# Sensor_HallArray.net
KiCad netlist of a schematic drawn in EAGLE
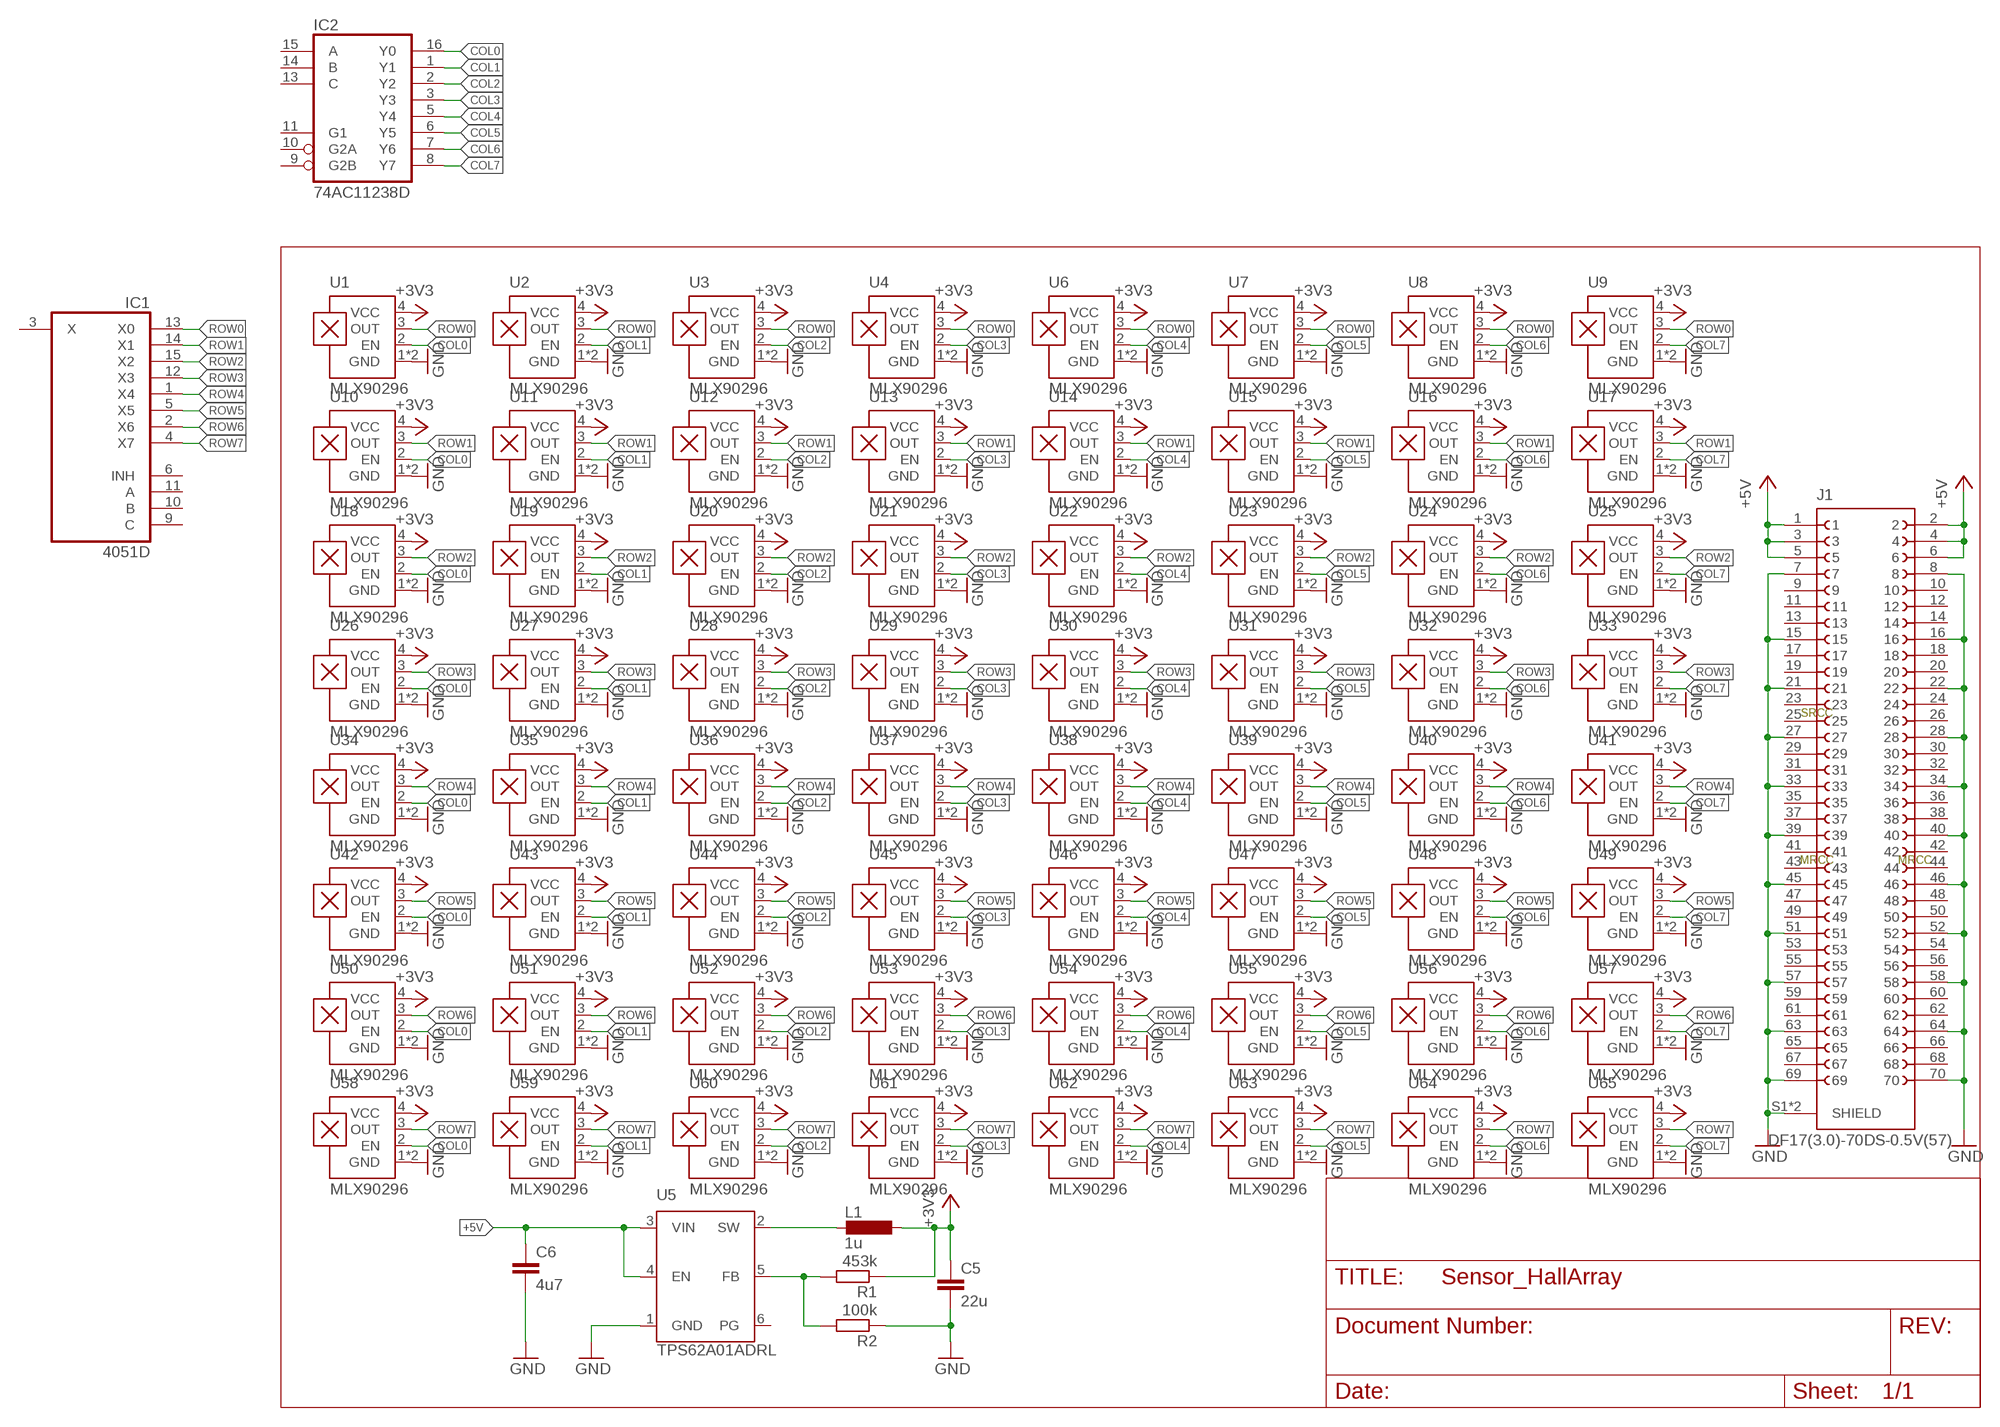
[diagram p0: schematic, sheet 1]

(export (version "E")
  (design (tool "Eeschema 10.0.6"))
  (components
    (comp (ref "C5")
      (value "22u")
      (footprint "eagle-import:C0603")
      (libsource (lib "eagle-import") (part "C-EUC0603"))
    )
    (comp (ref "C6")
      (value "4u7")
      (footprint "eagle-import:C0603")
      (libsource (lib "eagle-import") (part "C-EUC0603"))
    )
    (comp (ref "IC1")
      (value "4051D")
      (footprint "eagle-import:SO16")
      (libsource (lib "eagle-import") (part "4051D"))
    )
    (comp (ref "IC2")
      (value "74AC11238D")
      (footprint "eagle-import:SO16")
      (libsource (lib "eagle-import") (part "74AC11238D"))
    )
    (comp (ref "J1")
      (value "DF17(3.0)-70DS-0.5V(57)")
      (footprint "eagle-import:DF17(3.0)-70DS-0.5V(57)")
      (libsource (lib "eagle-import") (part "DF17(3.0)-70DS-0.5V(57)"))
    )
    (comp (ref "L1")
      (value "1u")
      (footprint "eagle-import:L1008")
      (fields (field (name "MPN") "LQM2HPN1R0MG0L"))
      (libsource (lib "eagle-import") (part "L-EU1008"))
    )
    (comp (ref "R1")
      (value "453k")
      (footprint "eagle-import:R0402")
      (libsource (lib "eagle-import") (part "R-EU_R0402"))
    )
    (comp (ref "R2")
      (value "100k")
      (footprint "eagle-import:R0402")
      (libsource (lib "eagle-import") (part "R-EU_R0402"))
    )
    (comp (ref "U1")
      (value "MLX90296")
      (footprint "eagle-import:DFN120X160X40-4")
      (libsource (lib "eagle-import") (part "MLX90296"))
    )
    (comp (ref "U2")
      (value "MLX90296")
      (footprint "eagle-import:DFN120X160X40-4")
      (libsource (lib "eagle-import") (part "MLX90296"))
    )
    (comp (ref "U3")
      (value "MLX90296")
      (footprint "eagle-import:DFN120X160X40-4")
      (libsource (lib "eagle-import") (part "MLX90296"))
    )
    (comp (ref "U4")
      (value "MLX90296")
      (footprint "eagle-import:DFN120X160X40-4")
      (libsource (lib "eagle-import") (part "MLX90296"))
    )
    (comp (ref "U5")
      (value "TPS62A01ADRL")
      (footprint "eagle-import:SOTFL50P160X60-6N")
      (fields (field (name "MANUFACTURER_PART_NUMBER") "TPS62A01ADRLR"))
      (libsource (lib "eagle-import") (part "TPS62A01ADRL"))
    )
    (comp (ref "U6")
      (value "MLX90296")
      (footprint "eagle-import:DFN120X160X40-4")
      (libsource (lib "eagle-import") (part "MLX90296"))
    )
    (comp (ref "U7")
      (value "MLX90296")
      (footprint "eagle-import:DFN120X160X40-4")
      (libsource (lib "eagle-import") (part "MLX90296"))
    )
    (comp (ref "U8")
      (value "MLX90296")
      (footprint "eagle-import:DFN120X160X40-4")
      (libsource (lib "eagle-import") (part "MLX90296"))
    )
    (comp (ref "U9")
      (value "MLX90296")
      (footprint "eagle-import:DFN120X160X40-4")
      (libsource (lib "eagle-import") (part "MLX90296"))
    )
    (comp (ref "U10")
      (value "MLX90296")
      (footprint "eagle-import:DFN120X160X40-4")
      (libsource (lib "eagle-import") (part "MLX90296"))
    )
    (comp (ref "U11")
      (value "MLX90296")
      (footprint "eagle-import:DFN120X160X40-4")
      (libsource (lib "eagle-import") (part "MLX90296"))
    )
    (comp (ref "U12")
      (value "MLX90296")
      (footprint "eagle-import:DFN120X160X40-4")
      (libsource (lib "eagle-import") (part "MLX90296"))
    )
    (comp (ref "U13")
      (value "MLX90296")
      (footprint "eagle-import:DFN120X160X40-4")
      (libsource (lib "eagle-import") (part "MLX90296"))
    )
    (comp (ref "U14")
      (value "MLX90296")
      (footprint "eagle-import:DFN120X160X40-4")
      (libsource (lib "eagle-import") (part "MLX90296"))
    )
    (comp (ref "U15")
      (value "MLX90296")
      (footprint "eagle-import:DFN120X160X40-4")
      (libsource (lib "eagle-import") (part "MLX90296"))
    )
    (comp (ref "U16")
      (value "MLX90296")
      (footprint "eagle-import:DFN120X160X40-4")
      (libsource (lib "eagle-import") (part "MLX90296"))
    )
    (comp (ref "U17")
      (value "MLX90296")
      (footprint "eagle-import:DFN120X160X40-4")
      (libsource (lib "eagle-import") (part "MLX90296"))
    )
    (comp (ref "U18")
      (value "MLX90296")
      (footprint "eagle-import:DFN120X160X40-4")
      (libsource (lib "eagle-import") (part "MLX90296"))
    )
    (comp (ref "U19")
      (value "MLX90296")
      (footprint "eagle-import:DFN120X160X40-4")
      (libsource (lib "eagle-import") (part "MLX90296"))
    )
    (comp (ref "U20")
      (value "MLX90296")
      (footprint "eagle-import:DFN120X160X40-4")
      (libsource (lib "eagle-import") (part "MLX90296"))
    )
    (comp (ref "U21")
      (value "MLX90296")
      (footprint "eagle-import:DFN120X160X40-4")
      (libsource (lib "eagle-import") (part "MLX90296"))
    )
    (comp (ref "U22")
      (value "MLX90296")
      (footprint "eagle-import:DFN120X160X40-4")
      (libsource (lib "eagle-import") (part "MLX90296"))
    )
    (comp (ref "U23")
      (value "MLX90296")
      (footprint "eagle-import:DFN120X160X40-4")
      (libsource (lib "eagle-import") (part "MLX90296"))
    )
    (comp (ref "U24")
      (value "MLX90296")
      (footprint "eagle-import:DFN120X160X40-4")
      (libsource (lib "eagle-import") (part "MLX90296"))
    )
    (comp (ref "U25")
      (value "MLX90296")
      (footprint "eagle-import:DFN120X160X40-4")
      (libsource (lib "eagle-import") (part "MLX90296"))
    )
    (comp (ref "U26")
      (value "MLX90296")
      (footprint "eagle-import:DFN120X160X40-4")
      (libsource (lib "eagle-import") (part "MLX90296"))
    )
    (comp (ref "U27")
      (value "MLX90296")
      (footprint "eagle-import:DFN120X160X40-4")
      (libsource (lib "eagle-import") (part "MLX90296"))
    )
    (comp (ref "U28")
      (value "MLX90296")
      (footprint "eagle-import:DFN120X160X40-4")
      (libsource (lib "eagle-import") (part "MLX90296"))
    )
    (comp (ref "U29")
      (value "MLX90296")
      (footprint "eagle-import:DFN120X160X40-4")
      (libsource (lib "eagle-import") (part "MLX90296"))
    )
    (comp (ref "U30")
      (value "MLX90296")
      (footprint "eagle-import:DFN120X160X40-4")
      (libsource (lib "eagle-import") (part "MLX90296"))
    )
    (comp (ref "U31")
      (value "MLX90296")
      (footprint "eagle-import:DFN120X160X40-4")
      (libsource (lib "eagle-import") (part "MLX90296"))
    )
    (comp (ref "U32")
      (value "MLX90296")
      (footprint "eagle-import:DFN120X160X40-4")
      (libsource (lib "eagle-import") (part "MLX90296"))
    )
    (comp (ref "U33")
      (value "MLX90296")
      (footprint "eagle-import:DFN120X160X40-4")
      (libsource (lib "eagle-import") (part "MLX90296"))
    )
    (comp (ref "U34")
      (value "MLX90296")
      (footprint "eagle-import:DFN120X160X40-4")
      (libsource (lib "eagle-import") (part "MLX90296"))
    )
    (comp (ref "U35")
      (value "MLX90296")
      (footprint "eagle-import:DFN120X160X40-4")
      (libsource (lib "eagle-import") (part "MLX90296"))
    )
    (comp (ref "U36")
      (value "MLX90296")
      (footprint "eagle-import:DFN120X160X40-4")
      (libsource (lib "eagle-import") (part "MLX90296"))
    )
    (comp (ref "U37")
      (value "MLX90296")
      (footprint "eagle-import:DFN120X160X40-4")
      (libsource (lib "eagle-import") (part "MLX90296"))
    )
    (comp (ref "U38")
      (value "MLX90296")
      (footprint "eagle-import:DFN120X160X40-4")
      (libsource (lib "eagle-import") (part "MLX90296"))
    )
    (comp (ref "U39")
      (value "MLX90296")
      (footprint "eagle-import:DFN120X160X40-4")
      (libsource (lib "eagle-import") (part "MLX90296"))
    )
    (comp (ref "U40")
      (value "MLX90296")
      (footprint "eagle-import:DFN120X160X40-4")
      (libsource (lib "eagle-import") (part "MLX90296"))
    )
    (comp (ref "U41")
      (value "MLX90296")
      (footprint "eagle-import:DFN120X160X40-4")
      (libsource (lib "eagle-import") (part "MLX90296"))
    )
    (comp (ref "U42")
      (value "MLX90296")
      (footprint "eagle-import:DFN120X160X40-4")
      (libsource (lib "eagle-import") (part "MLX90296"))
    )
    (comp (ref "U43")
      (value "MLX90296")
      (footprint "eagle-import:DFN120X160X40-4")
      (libsource (lib "eagle-import") (part "MLX90296"))
    )
    (comp (ref "U44")
      (value "MLX90296")
      (footprint "eagle-import:DFN120X160X40-4")
      (libsource (lib "eagle-import") (part "MLX90296"))
    )
    (comp (ref "U45")
      (value "MLX90296")
      (footprint "eagle-import:DFN120X160X40-4")
      (libsource (lib "eagle-import") (part "MLX90296"))
    )
    (comp (ref "U46")
      (value "MLX90296")
      (footprint "eagle-import:DFN120X160X40-4")
      (libsource (lib "eagle-import") (part "MLX90296"))
    )
    (comp (ref "U47")
      (value "MLX90296")
      (footprint "eagle-import:DFN120X160X40-4")
      (libsource (lib "eagle-import") (part "MLX90296"))
    )
    (comp (ref "U48")
      (value "MLX90296")
      (footprint "eagle-import:DFN120X160X40-4")
      (libsource (lib "eagle-import") (part "MLX90296"))
    )
    (comp (ref "U49")
      (value "MLX90296")
      (footprint "eagle-import:DFN120X160X40-4")
      (libsource (lib "eagle-import") (part "MLX90296"))
    )
    (comp (ref "U50")
      (value "MLX90296")
      (footprint "eagle-import:DFN120X160X40-4")
      (libsource (lib "eagle-import") (part "MLX90296"))
    )
    (comp (ref "U51")
      (value "MLX90296")
      (footprint "eagle-import:DFN120X160X40-4")
      (libsource (lib "eagle-import") (part "MLX90296"))
    )
    (comp (ref "U52")
      (value "MLX90296")
      (footprint "eagle-import:DFN120X160X40-4")
      (libsource (lib "eagle-import") (part "MLX90296"))
    )
    (comp (ref "U53")
      (value "MLX90296")
      (footprint "eagle-import:DFN120X160X40-4")
      (libsource (lib "eagle-import") (part "MLX90296"))
    )
    (comp (ref "U54")
      (value "MLX90296")
      (footprint "eagle-import:DFN120X160X40-4")
      (libsource (lib "eagle-import") (part "MLX90296"))
    )
    (comp (ref "U55")
      (value "MLX90296")
      (footprint "eagle-import:DFN120X160X40-4")
      (libsource (lib "eagle-import") (part "MLX90296"))
    )
    (comp (ref "U56")
      (value "MLX90296")
      (footprint "eagle-import:DFN120X160X40-4")
      (libsource (lib "eagle-import") (part "MLX90296"))
    )
    (comp (ref "U57")
      (value "MLX90296")
      (footprint "eagle-import:DFN120X160X40-4")
      (libsource (lib "eagle-import") (part "MLX90296"))
    )
    (comp (ref "U58")
      (value "MLX90296")
      (footprint "eagle-import:DFN120X160X40-4")
      (libsource (lib "eagle-import") (part "MLX90296"))
    )
    (comp (ref "U59")
      (value "MLX90296")
      (footprint "eagle-import:DFN120X160X40-4")
      (libsource (lib "eagle-import") (part "MLX90296"))
    )
    (comp (ref "U60")
      (value "MLX90296")
      (footprint "eagle-import:DFN120X160X40-4")
      (libsource (lib "eagle-import") (part "MLX90296"))
    )
    (comp (ref "U61")
      (value "MLX90296")
      (footprint "eagle-import:DFN120X160X40-4")
      (libsource (lib "eagle-import") (part "MLX90296"))
    )
    (comp (ref "U62")
      (value "MLX90296")
      (footprint "eagle-import:DFN120X160X40-4")
      (libsource (lib "eagle-import") (part "MLX90296"))
    )
    (comp (ref "U63")
      (value "MLX90296")
      (footprint "eagle-import:DFN120X160X40-4")
      (libsource (lib "eagle-import") (part "MLX90296"))
    )
    (comp (ref "U64")
      (value "MLX90296")
      (footprint "eagle-import:DFN120X160X40-4")
      (libsource (lib "eagle-import") (part "MLX90296"))
    )
    (comp (ref "U65")
      (value "MLX90296")
      (footprint "eagle-import:DFN120X160X40-4")
      (libsource (lib "eagle-import") (part "MLX90296"))
    )
  )
  (nets
    (net (code "1") (name "+3V3") (class "Default")
      (node (ref "C5") (pin "1") (pinfunction "1_1") (pintype "passive"))
      (node (ref "L1") (pin "1") (pinfunction "1_1") (pintype "passive"))
      (node (ref "R1") (pin "1") (pinfunction "1_1") (pintype "passive"))
      (node (ref "U1") (pin "4") (pinfunction "VCC_4") (pintype "power_in"))
      (node (ref "U10") (pin "4") (pinfunction "VCC_4") (pintype "power_in"))
      (node (ref "U11") (pin "4") (pinfunction "VCC_4") (pintype "power_in"))
      (node (ref "U12") (pin "4") (pinfunction "VCC_4") (pintype "power_in"))
      (node (ref "U13") (pin "4") (pinfunction "VCC_4") (pintype "power_in"))
      (node (ref "U14") (pin "4") (pinfunction "VCC_4") (pintype "power_in"))
      (node (ref "U15") (pin "4") (pinfunction "VCC_4") (pintype "power_in"))
      (node (ref "U16") (pin "4") (pinfunction "VCC_4") (pintype "power_in"))
      (node (ref "U17") (pin "4") (pinfunction "VCC_4") (pintype "power_in"))
      (node (ref "U18") (pin "4") (pinfunction "VCC_4") (pintype "power_in"))
      (node (ref "U19") (pin "4") (pinfunction "VCC_4") (pintype "power_in"))
      (node (ref "U2") (pin "4") (pinfunction "VCC_4") (pintype "power_in"))
      (node (ref "U20") (pin "4") (pinfunction "VCC_4") (pintype "power_in"))
      (node (ref "U21") (pin "4") (pinfunction "VCC_4") (pintype "power_in"))
      (node (ref "U22") (pin "4") (pinfunction "VCC_4") (pintype "power_in"))
      (node (ref "U23") (pin "4") (pinfunction "VCC_4") (pintype "power_in"))
      (node (ref "U24") (pin "4") (pinfunction "VCC_4") (pintype "power_in"))
      (node (ref "U25") (pin "4") (pinfunction "VCC_4") (pintype "power_in"))
      (node (ref "U26") (pin "4") (pinfunction "VCC_4") (pintype "power_in"))
      (node (ref "U27") (pin "4") (pinfunction "VCC_4") (pintype "power_in"))
      (node (ref "U28") (pin "4") (pinfunction "VCC_4") (pintype "power_in"))
      (node (ref "U29") (pin "4") (pinfunction "VCC_4") (pintype "power_in"))
      (node (ref "U3") (pin "4") (pinfunction "VCC_4") (pintype "power_in"))
      (node (ref "U30") (pin "4") (pinfunction "VCC_4") (pintype "power_in"))
      (node (ref "U31") (pin "4") (pinfunction "VCC_4") (pintype "power_in"))
      (node (ref "U32") (pin "4") (pinfunction "VCC_4") (pintype "power_in"))
      (node (ref "U33") (pin "4") (pinfunction "VCC_4") (pintype "power_in"))
      (node (ref "U34") (pin "4") (pinfunction "VCC_4") (pintype "power_in"))
      (node (ref "U35") (pin "4") (pinfunction "VCC_4") (pintype "power_in"))
      (node (ref "U36") (pin "4") (pinfunction "VCC_4") (pintype "power_in"))
      (node (ref "U37") (pin "4") (pinfunction "VCC_4") (pintype "power_in"))
      (node (ref "U38") (pin "4") (pinfunction "VCC_4") (pintype "power_in"))
      (node (ref "U39") (pin "4") (pinfunction "VCC_4") (pintype "power_in"))
      (node (ref "U4") (pin "4") (pinfunction "VCC_4") (pintype "power_in"))
      (node (ref "U40") (pin "4") (pinfunction "VCC_4") (pintype "power_in"))
      (node (ref "U41") (pin "4") (pinfunction "VCC_4") (pintype "power_in"))
      (node (ref "U42") (pin "4") (pinfunction "VCC_4") (pintype "power_in"))
      (node (ref "U43") (pin "4") (pinfunction "VCC_4") (pintype "power_in"))
      (node (ref "U44") (pin "4") (pinfunction "VCC_4") (pintype "power_in"))
      (node (ref "U45") (pin "4") (pinfunction "VCC_4") (pintype "power_in"))
      (node (ref "U46") (pin "4") (pinfunction "VCC_4") (pintype "power_in"))
      (node (ref "U47") (pin "4") (pinfunction "VCC_4") (pintype "power_in"))
      (node (ref "U48") (pin "4") (pinfunction "VCC_4") (pintype "power_in"))
      (node (ref "U49") (pin "4") (pinfunction "VCC_4") (pintype "power_in"))
      (node (ref "U50") (pin "4") (pinfunction "VCC_4") (pintype "power_in"))
      (node (ref "U51") (pin "4") (pinfunction "VCC_4") (pintype "power_in"))
      (node (ref "U52") (pin "4") (pinfunction "VCC_4") (pintype "power_in"))
      (node (ref "U53") (pin "4") (pinfunction "VCC_4") (pintype "power_in"))
      (node (ref "U54") (pin "4") (pinfunction "VCC_4") (pintype "power_in"))
      (node (ref "U55") (pin "4") (pinfunction "VCC_4") (pintype "power_in"))
      (node (ref "U56") (pin "4") (pinfunction "VCC_4") (pintype "power_in"))
      (node (ref "U57") (pin "4") (pinfunction "VCC_4") (pintype "power_in"))
      (node (ref "U58") (pin "4") (pinfunction "VCC_4") (pintype "power_in"))
      (node (ref "U59") (pin "4") (pinfunction "VCC_4") (pintype "power_in"))
      (node (ref "U6") (pin "4") (pinfunction "VCC_4") (pintype "power_in"))
      (node (ref "U60") (pin "4") (pinfunction "VCC_4") (pintype "power_in"))
      (node (ref "U61") (pin "4") (pinfunction "VCC_4") (pintype "power_in"))
      (node (ref "U62") (pin "4") (pinfunction "VCC_4") (pintype "power_in"))
      (node (ref "U63") (pin "4") (pinfunction "VCC_4") (pintype "power_in"))
      (node (ref "U64") (pin "4") (pinfunction "VCC_4") (pintype "power_in"))
      (node (ref "U65") (pin "4") (pinfunction "VCC_4") (pintype "power_in"))
      (node (ref "U7") (pin "4") (pinfunction "VCC_4") (pintype "power_in"))
      (node (ref "U8") (pin "4") (pinfunction "VCC_4") (pintype "power_in"))
      (node (ref "U9") (pin "4") (pinfunction "VCC_4") (pintype "power_in"))
    )
    (net (code "2") (name "+5V") (class "Default")
      (node (ref "C6") (pin "1") (pinfunction "1_1") (pintype "passive"))
      (node (ref "J1") (pin "1") (pinfunction "1_1") (pintype "passive"))
      (node (ref "J1") (pin "2") (pinfunction "2_2") (pintype "passive"))
      (node (ref "J1") (pin "3") (pinfunction "3_3") (pintype "passive"))
      (node (ref "J1") (pin "4") (pinfunction "4_4") (pintype "passive"))
      (node (ref "J1") (pin "5") (pinfunction "5_5") (pintype "passive"))
      (node (ref "J1") (pin "6") (pinfunction "6_6") (pintype "passive"))
      (node (ref "U5") (pin "3") (pinfunction "VIN_3") (pintype "bidirectional"))
      (node (ref "U5") (pin "4") (pinfunction "EN_4") (pintype "bidirectional"))
    )
    (net (code "3") (name "COL0") (class "Default")
      (node (ref "IC2") (pin "16") (pinfunction "Y0_16") (pintype "output"))
      (node (ref "U1") (pin "2") (pinfunction "EN_2") (pintype "input"))
      (node (ref "U10") (pin "2") (pinfunction "EN_2") (pintype "input"))
      (node (ref "U18") (pin "2") (pinfunction "EN_2") (pintype "input"))
      (node (ref "U26") (pin "2") (pinfunction "EN_2") (pintype "input"))
      (node (ref "U34") (pin "2") (pinfunction "EN_2") (pintype "input"))
      (node (ref "U42") (pin "2") (pinfunction "EN_2") (pintype "input"))
      (node (ref "U50") (pin "2") (pinfunction "EN_2") (pintype "input"))
      (node (ref "U58") (pin "2") (pinfunction "EN_2") (pintype "input"))
    )
    (net (code "4") (name "COL1") (class "Default")
      (node (ref "IC2") (pin "1") (pinfunction "Y1_1") (pintype "output"))
      (node (ref "U11") (pin "2") (pinfunction "EN_2") (pintype "input"))
      (node (ref "U19") (pin "2") (pinfunction "EN_2") (pintype "input"))
      (node (ref "U2") (pin "2") (pinfunction "EN_2") (pintype "input"))
      (node (ref "U27") (pin "2") (pinfunction "EN_2") (pintype "input"))
      (node (ref "U35") (pin "2") (pinfunction "EN_2") (pintype "input"))
      (node (ref "U43") (pin "2") (pinfunction "EN_2") (pintype "input"))
      (node (ref "U51") (pin "2") (pinfunction "EN_2") (pintype "input"))
      (node (ref "U59") (pin "2") (pinfunction "EN_2") (pintype "input"))
    )
    (net (code "5") (name "COL2") (class "Default")
      (node (ref "IC2") (pin "2") (pinfunction "Y2_2") (pintype "output"))
      (node (ref "U12") (pin "2") (pinfunction "EN_2") (pintype "input"))
      (node (ref "U20") (pin "2") (pinfunction "EN_2") (pintype "input"))
      (node (ref "U28") (pin "2") (pinfunction "EN_2") (pintype "input"))
      (node (ref "U3") (pin "2") (pinfunction "EN_2") (pintype "input"))
      (node (ref "U36") (pin "2") (pinfunction "EN_2") (pintype "input"))
      (node (ref "U44") (pin "2") (pinfunction "EN_2") (pintype "input"))
      (node (ref "U52") (pin "2") (pinfunction "EN_2") (pintype "input"))
      (node (ref "U60") (pin "2") (pinfunction "EN_2") (pintype "input"))
    )
    (net (code "6") (name "COL3") (class "Default")
      (node (ref "IC2") (pin "3") (pinfunction "Y3_3") (pintype "output"))
      (node (ref "U13") (pin "2") (pinfunction "EN_2") (pintype "input"))
      (node (ref "U21") (pin "2") (pinfunction "EN_2") (pintype "input"))
      (node (ref "U29") (pin "2") (pinfunction "EN_2") (pintype "input"))
      (node (ref "U37") (pin "2") (pinfunction "EN_2") (pintype "input"))
      (node (ref "U4") (pin "2") (pinfunction "EN_2") (pintype "input"))
      (node (ref "U45") (pin "2") (pinfunction "EN_2") (pintype "input"))
      (node (ref "U53") (pin "2") (pinfunction "EN_2") (pintype "input"))
      (node (ref "U61") (pin "2") (pinfunction "EN_2") (pintype "input"))
    )
    (net (code "7") (name "COL4") (class "Default")
      (node (ref "IC2") (pin "5") (pinfunction "Y4_5") (pintype "output"))
      (node (ref "U14") (pin "2") (pinfunction "EN_2") (pintype "input"))
      (node (ref "U22") (pin "2") (pinfunction "EN_2") (pintype "input"))
      (node (ref "U30") (pin "2") (pinfunction "EN_2") (pintype "input"))
      (node (ref "U38") (pin "2") (pinfunction "EN_2") (pintype "input"))
      (node (ref "U46") (pin "2") (pinfunction "EN_2") (pintype "input"))
      (node (ref "U54") (pin "2") (pinfunction "EN_2") (pintype "input"))
      (node (ref "U6") (pin "2") (pinfunction "EN_2") (pintype "input"))
      (node (ref "U62") (pin "2") (pinfunction "EN_2") (pintype "input"))
    )
    (net (code "8") (name "COL5") (class "Default")
      (node (ref "IC2") (pin "6") (pinfunction "Y5_6") (pintype "output"))
      (node (ref "U15") (pin "2") (pinfunction "EN_2") (pintype "input"))
      (node (ref "U23") (pin "2") (pinfunction "EN_2") (pintype "input"))
      (node (ref "U31") (pin "2") (pinfunction "EN_2") (pintype "input"))
      (node (ref "U39") (pin "2") (pinfunction "EN_2") (pintype "input"))
      (node (ref "U47") (pin "2") (pinfunction "EN_2") (pintype "input"))
      (node (ref "U55") (pin "2") (pinfunction "EN_2") (pintype "input"))
      (node (ref "U63") (pin "2") (pinfunction "EN_2") (pintype "input"))
      (node (ref "U7") (pin "2") (pinfunction "EN_2") (pintype "input"))
    )
    (net (code "9") (name "COL6") (class "Default")
      (node (ref "IC2") (pin "7") (pinfunction "Y6_7") (pintype "output"))
      (node (ref "U16") (pin "2") (pinfunction "EN_2") (pintype "input"))
      (node (ref "U24") (pin "2") (pinfunction "EN_2") (pintype "input"))
      (node (ref "U32") (pin "2") (pinfunction "EN_2") (pintype "input"))
      (node (ref "U40") (pin "2") (pinfunction "EN_2") (pintype "input"))
      (node (ref "U48") (pin "2") (pinfunction "EN_2") (pintype "input"))
      (node (ref "U56") (pin "2") (pinfunction "EN_2") (pintype "input"))
      (node (ref "U64") (pin "2") (pinfunction "EN_2") (pintype "input"))
      (node (ref "U8") (pin "2") (pinfunction "EN_2") (pintype "input"))
    )
    (net (code "10") (name "COL7") (class "Default")
      (node (ref "IC2") (pin "8") (pinfunction "Y7_8") (pintype "output"))
      (node (ref "U17") (pin "2") (pinfunction "EN_2") (pintype "input"))
      (node (ref "U25") (pin "2") (pinfunction "EN_2") (pintype "input"))
      (node (ref "U33") (pin "2") (pinfunction "EN_2") (pintype "input"))
      (node (ref "U41") (pin "2") (pinfunction "EN_2") (pintype "input"))
      (node (ref "U49") (pin "2") (pinfunction "EN_2") (pintype "input"))
      (node (ref "U57") (pin "2") (pinfunction "EN_2") (pintype "input"))
      (node (ref "U65") (pin "2") (pinfunction "EN_2") (pintype "input"))
      (node (ref "U9") (pin "2") (pinfunction "EN_2") (pintype "input"))
    )
    (net (code "11") (name "GND") (class "Default")
      (node (ref "C5") (pin "2") (pinfunction "2_2") (pintype "passive"))
      (node (ref "C6") (pin "2") (pinfunction "2_2") (pintype "passive"))
      (node (ref "J1") (pin "15") (pinfunction "15_15") (pintype "passive"))
      (node (ref "J1") (pin "16") (pinfunction "16_16") (pintype "passive"))
      (node (ref "J1") (pin "21") (pinfunction "21_21") (pintype "passive"))
      (node (ref "J1") (pin "22") (pinfunction "22_22") (pintype "passive"))
      (node (ref "J1") (pin "27") (pinfunction "27_27") (pintype "passive"))
      (node (ref "J1") (pin "28") (pinfunction "28_28") (pintype "passive"))
      (node (ref "J1") (pin "33") (pinfunction "33_33") (pintype "passive"))
      (node (ref "J1") (pin "34") (pinfunction "34_34") (pintype "passive"))
      (node (ref "J1") (pin "39") (pinfunction "39_39") (pintype "passive"))
      (node (ref "J1") (pin "40") (pinfunction "40_40") (pintype "passive"))
      (node (ref "J1") (pin "45") (pinfunction "45_45") (pintype "passive"))
      (node (ref "J1") (pin "46") (pinfunction "46_46") (pintype "passive"))
      (node (ref "J1") (pin "51") (pinfunction "51_51") (pintype "passive"))
      (node (ref "J1") (pin "52") (pinfunction "52_52") (pintype "passive"))
      (node (ref "J1") (pin "57") (pinfunction "57_57") (pintype "passive"))
      (node (ref "J1") (pin "58") (pinfunction "58_58") (pintype "passive"))
      (node (ref "J1") (pin "63") (pinfunction "63_63") (pintype "passive"))
      (node (ref "J1") (pin "64") (pinfunction "64_64") (pintype "passive"))
      (node (ref "J1") (pin "69") (pinfunction "69_69") (pintype "passive"))
      (node (ref "J1") (pin "7") (pinfunction "7_7") (pintype "passive"))
      (node (ref "J1") (pin "70") (pinfunction "70_70") (pintype "passive"))
      (node (ref "J1") (pin "8") (pinfunction "8_8") (pintype "passive"))
      (node (ref "J1") (pin "S1") (pinfunction "SHIELD_S1") (pintype "passive"))
      (node (ref "J1") (pin "S2") (pinfunction "SHIELD_S2") (pintype "passive"))
      (node (ref "R2") (pin "1") (pinfunction "1_1") (pintype "passive"))
      (node (ref "U1") (pin "1") (pinfunction "GND_1") (pintype "power_in"))
      (node (ref "U1") (pin "E") (pinfunction "GND_E") (pintype "power_in"))
      (node (ref "U10") (pin "1") (pinfunction "GND_1") (pintype "power_in"))
      (node (ref "U10") (pin "E") (pinfunction "GND_E") (pintype "power_in"))
      (node (ref "U11") (pin "1") (pinfunction "GND_1") (pintype "power_in"))
      (node (ref "U11") (pin "E") (pinfunction "GND_E") (pintype "power_in"))
      (node (ref "U12") (pin "1") (pinfunction "GND_1") (pintype "power_in"))
      (node (ref "U12") (pin "E") (pinfunction "GND_E") (pintype "power_in"))
      (node (ref "U13") (pin "1") (pinfunction "GND_1") (pintype "power_in"))
      (node (ref "U13") (pin "E") (pinfunction "GND_E") (pintype "power_in"))
      (node (ref "U14") (pin "1") (pinfunction "GND_1") (pintype "power_in"))
      (node (ref "U14") (pin "E") (pinfunction "GND_E") (pintype "power_in"))
      (node (ref "U15") (pin "1") (pinfunction "GND_1") (pintype "power_in"))
      (node (ref "U15") (pin "E") (pinfunction "GND_E") (pintype "power_in"))
      (node (ref "U16") (pin "1") (pinfunction "GND_1") (pintype "power_in"))
      (node (ref "U16") (pin "E") (pinfunction "GND_E") (pintype "power_in"))
      (node (ref "U17") (pin "1") (pinfunction "GND_1") (pintype "power_in"))
      (node (ref "U17") (pin "E") (pinfunction "GND_E") (pintype "power_in"))
      (node (ref "U18") (pin "1") (pinfunction "GND_1") (pintype "power_in"))
      (node (ref "U18") (pin "E") (pinfunction "GND_E") (pintype "power_in"))
      (node (ref "U19") (pin "1") (pinfunction "GND_1") (pintype "power_in"))
      (node (ref "U19") (pin "E") (pinfunction "GND_E") (pintype "power_in"))
      (node (ref "U2") (pin "1") (pinfunction "GND_1") (pintype "power_in"))
      (node (ref "U2") (pin "E") (pinfunction "GND_E") (pintype "power_in"))
      (node (ref "U20") (pin "1") (pinfunction "GND_1") (pintype "power_in"))
      (node (ref "U20") (pin "E") (pinfunction "GND_E") (pintype "power_in"))
      (node (ref "U21") (pin "1") (pinfunction "GND_1") (pintype "power_in"))
      (node (ref "U21") (pin "E") (pinfunction "GND_E") (pintype "power_in"))
      (node (ref "U22") (pin "1") (pinfunction "GND_1") (pintype "power_in"))
      (node (ref "U22") (pin "E") (pinfunction "GND_E") (pintype "power_in"))
      (node (ref "U23") (pin "1") (pinfunction "GND_1") (pintype "power_in"))
      (node (ref "U23") (pin "E") (pinfunction "GND_E") (pintype "power_in"))
      (node (ref "U24") (pin "1") (pinfunction "GND_1") (pintype "power_in"))
      (node (ref "U24") (pin "E") (pinfunction "GND_E") (pintype "power_in"))
      (node (ref "U25") (pin "1") (pinfunction "GND_1") (pintype "power_in"))
      (node (ref "U25") (pin "E") (pinfunction "GND_E") (pintype "power_in"))
      (node (ref "U26") (pin "1") (pinfunction "GND_1") (pintype "power_in"))
      (node (ref "U26") (pin "E") (pinfunction "GND_E") (pintype "power_in"))
      (node (ref "U27") (pin "1") (pinfunction "GND_1") (pintype "power_in"))
      (node (ref "U27") (pin "E") (pinfunction "GND_E") (pintype "power_in"))
      (node (ref "U28") (pin "1") (pinfunction "GND_1") (pintype "power_in"))
      (node (ref "U28") (pin "E") (pinfunction "GND_E") (pintype "power_in"))
      (node (ref "U29") (pin "1") (pinfunction "GND_1") (pintype "power_in"))
      (node (ref "U29") (pin "E") (pinfunction "GND_E") (pintype "power_in"))
      (node (ref "U3") (pin "1") (pinfunction "GND_1") (pintype "power_in"))
      (node (ref "U3") (pin "E") (pinfunction "GND_E") (pintype "power_in"))
      (node (ref "U30") (pin "1") (pinfunction "GND_1") (pintype "power_in"))
      (node (ref "U30") (pin "E") (pinfunction "GND_E") (pintype "power_in"))
      (node (ref "U31") (pin "1") (pinfunction "GND_1") (pintype "power_in"))
      (node (ref "U31") (pin "E") (pinfunction "GND_E") (pintype "power_in"))
      (node (ref "U32") (pin "1") (pinfunction "GND_1") (pintype "power_in"))
      (node (ref "U32") (pin "E") (pinfunction "GND_E") (pintype "power_in"))
      (node (ref "U33") (pin "1") (pinfunction "GND_1") (pintype "power_in"))
      (node (ref "U33") (pin "E") (pinfunction "GND_E") (pintype "power_in"))
      (node (ref "U34") (pin "1") (pinfunction "GND_1") (pintype "power_in"))
      (node (ref "U34") (pin "E") (pinfunction "GND_E") (pintype "power_in"))
      (node (ref "U35") (pin "1") (pinfunction "GND_1") (pintype "power_in"))
      (node (ref "U35") (pin "E") (pinfunction "GND_E") (pintype "power_in"))
      (node (ref "U36") (pin "1") (pinfunction "GND_1") (pintype "power_in"))
      (node (ref "U36") (pin "E") (pinfunction "GND_E") (pintype "power_in"))
      (node (ref "U37") (pin "1") (pinfunction "GND_1") (pintype "power_in"))
      (node (ref "U37") (pin "E") (pinfunction "GND_E") (pintype "power_in"))
      (node (ref "U38") (pin "1") (pinfunction "GND_1") (pintype "power_in"))
      (node (ref "U38") (pin "E") (pinfunction "GND_E") (pintype "power_in"))
      (node (ref "U39") (pin "1") (pinfunction "GND_1") (pintype "power_in"))
      (node (ref "U39") (pin "E") (pinfunction "GND_E") (pintype "power_in"))
      (node (ref "U4") (pin "1") (pinfunction "GND_1") (pintype "power_in"))
      (node (ref "U4") (pin "E") (pinfunction "GND_E") (pintype "power_in"))
      (node (ref "U40") (pin "1") (pinfunction "GND_1") (pintype "power_in"))
      (node (ref "U40") (pin "E") (pinfunction "GND_E") (pintype "power_in"))
      (node (ref "U41") (pin "1") (pinfunction "GND_1") (pintype "power_in"))
      (node (ref "U41") (pin "E") (pinfunction "GND_E") (pintype "power_in"))
      (node (ref "U42") (pin "1") (pinfunction "GND_1") (pintype "power_in"))
      (node (ref "U42") (pin "E") (pinfunction "GND_E") (pintype "power_in"))
      (node (ref "U43") (pin "1") (pinfunction "GND_1") (pintype "power_in"))
      (node (ref "U43") (pin "E") (pinfunction "GND_E") (pintype "power_in"))
      (node (ref "U44") (pin "1") (pinfunction "GND_1") (pintype "power_in"))
      (node (ref "U44") (pin "E") (pinfunction "GND_E") (pintype "power_in"))
      (node (ref "U45") (pin "1") (pinfunction "GND_1") (pintype "power_in"))
      (node (ref "U45") (pin "E") (pinfunction "GND_E") (pintype "power_in"))
      (node (ref "U46") (pin "1") (pinfunction "GND_1") (pintype "power_in"))
      (node (ref "U46") (pin "E") (pinfunction "GND_E") (pintype "power_in"))
      (node (ref "U47") (pin "1") (pinfunction "GND_1") (pintype "power_in"))
      (node (ref "U47") (pin "E") (pinfunction "GND_E") (pintype "power_in"))
      (node (ref "U48") (pin "1") (pinfunction "GND_1") (pintype "power_in"))
      (node (ref "U48") (pin "E") (pinfunction "GND_E") (pintype "power_in"))
      (node (ref "U49") (pin "1") (pinfunction "GND_1") (pintype "power_in"))
      (node (ref "U49") (pin "E") (pinfunction "GND_E") (pintype "power_in"))
      (node (ref "U5") (pin "1") (pinfunction "GND_1") (pintype "bidirectional"))
      (node (ref "U50") (pin "1") (pinfunction "GND_1") (pintype "power_in"))
      (node (ref "U50") (pin "E") (pinfunction "GND_E") (pintype "power_in"))
      (node (ref "U51") (pin "1") (pinfunction "GND_1") (pintype "power_in"))
      (node (ref "U51") (pin "E") (pinfunction "GND_E") (pintype "power_in"))
      (node (ref "U52") (pin "1") (pinfunction "GND_1") (pintype "power_in"))
      (node (ref "U52") (pin "E") (pinfunction "GND_E") (pintype "power_in"))
      (node (ref "U53") (pin "1") (pinfunction "GND_1") (pintype "power_in"))
      (node (ref "U53") (pin "E") (pinfunction "GND_E") (pintype "power_in"))
      (node (ref "U54") (pin "1") (pinfunction "GND_1") (pintype "power_in"))
      (node (ref "U54") (pin "E") (pinfunction "GND_E") (pintype "power_in"))
      (node (ref "U55") (pin "1") (pinfunction "GND_1") (pintype "power_in"))
      (node (ref "U55") (pin "E") (pinfunction "GND_E") (pintype "power_in"))
      (node (ref "U56") (pin "1") (pinfunction "GND_1") (pintype "power_in"))
      (node (ref "U56") (pin "E") (pinfunction "GND_E") (pintype "power_in"))
      (node (ref "U57") (pin "1") (pinfunction "GND_1") (pintype "power_in"))
      (node (ref "U57") (pin "E") (pinfunction "GND_E") (pintype "power_in"))
      (node (ref "U58") (pin "1") (pinfunction "GND_1") (pintype "power_in"))
      (node (ref "U58") (pin "E") (pinfunction "GND_E") (pintype "power_in"))
      (node (ref "U59") (pin "1") (pinfunction "GND_1") (pintype "power_in"))
      (node (ref "U59") (pin "E") (pinfunction "GND_E") (pintype "power_in"))
      (node (ref "U6") (pin "1") (pinfunction "GND_1") (pintype "power_in"))
      (node (ref "U6") (pin "E") (pinfunction "GND_E") (pintype "power_in"))
      (node (ref "U60") (pin "1") (pinfunction "GND_1") (pintype "power_in"))
      (node (ref "U60") (pin "E") (pinfunction "GND_E") (pintype "power_in"))
      (node (ref "U61") (pin "1") (pinfunction "GND_1") (pintype "power_in"))
      (node (ref "U61") (pin "E") (pinfunction "GND_E") (pintype "power_in"))
      (node (ref "U62") (pin "1") (pinfunction "GND_1") (pintype "power_in"))
      (node (ref "U62") (pin "E") (pinfunction "GND_E") (pintype "power_in"))
      (node (ref "U63") (pin "1") (pinfunction "GND_1") (pintype "power_in"))
      (node (ref "U63") (pin "E") (pinfunction "GND_E") (pintype "power_in"))
      (node (ref "U64") (pin "1") (pinfunction "GND_1") (pintype "power_in"))
      (node (ref "U64") (pin "E") (pinfunction "GND_E") (pintype "power_in"))
      (node (ref "U65") (pin "1") (pinfunction "GND_1") (pintype "power_in"))
      (node (ref "U65") (pin "E") (pinfunction "GND_E") (pintype "power_in"))
      (node (ref "U7") (pin "1") (pinfunction "GND_1") (pintype "power_in"))
      (node (ref "U7") (pin "E") (pinfunction "GND_E") (pintype "power_in"))
      (node (ref "U8") (pin "1") (pinfunction "GND_1") (pintype "power_in"))
      (node (ref "U8") (pin "E") (pinfunction "GND_E") (pintype "power_in"))
      (node (ref "U9") (pin "1") (pinfunction "GND_1") (pintype "power_in"))
      (node (ref "U9") (pin "E") (pinfunction "GND_E") (pintype "power_in"))
    )
    (net (code "12") (name "Net-(U5-FB)") (class "Default")
      (node (ref "R1") (pin "2") (pinfunction "2_2") (pintype "passive"))
      (node (ref "R2") (pin "2") (pinfunction "2_2") (pintype "passive"))
      (node (ref "U5") (pin "5") (pinfunction "FB_5") (pintype "bidirectional"))
    )
    (net (code "13") (name "Net-(U5-SW)") (class "Default")
      (node (ref "L1") (pin "2") (pinfunction "2_2") (pintype "passive"))
      (node (ref "U5") (pin "2") (pinfunction "SW_2") (pintype "bidirectional"))
    )
    (net (code "14") (name "ROW0") (class "Default")
      (node (ref "IC1") (pin "13") (pinfunction "X0_13") (pintype "bidirectional"))
      (node (ref "U1") (pin "3") (pinfunction "OUT_3") (pintype "output"))
      (node (ref "U2") (pin "3") (pinfunction "OUT_3") (pintype "output"))
      (node (ref "U3") (pin "3") (pinfunction "OUT_3") (pintype "output"))
      (node (ref "U4") (pin "3") (pinfunction "OUT_3") (pintype "output"))
      (node (ref "U6") (pin "3") (pinfunction "OUT_3") (pintype "output"))
      (node (ref "U7") (pin "3") (pinfunction "OUT_3") (pintype "output"))
      (node (ref "U8") (pin "3") (pinfunction "OUT_3") (pintype "output"))
      (node (ref "U9") (pin "3") (pinfunction "OUT_3") (pintype "output"))
    )
    (net (code "15") (name "ROW1") (class "Default")
      (node (ref "IC1") (pin "14") (pinfunction "X1_14") (pintype "bidirectional"))
      (node (ref "U10") (pin "3") (pinfunction "OUT_3") (pintype "output"))
      (node (ref "U11") (pin "3") (pinfunction "OUT_3") (pintype "output"))
      (node (ref "U12") (pin "3") (pinfunction "OUT_3") (pintype "output"))
      (node (ref "U13") (pin "3") (pinfunction "OUT_3") (pintype "output"))
      (node (ref "U14") (pin "3") (pinfunction "OUT_3") (pintype "output"))
      (node (ref "U15") (pin "3") (pinfunction "OUT_3") (pintype "output"))
      (node (ref "U16") (pin "3") (pinfunction "OUT_3") (pintype "output"))
      (node (ref "U17") (pin "3") (pinfunction "OUT_3") (pintype "output"))
    )
    (net (code "16") (name "ROW2") (class "Default")
      (node (ref "IC1") (pin "15") (pinfunction "X2_15") (pintype "bidirectional"))
      (node (ref "U18") (pin "3") (pinfunction "OUT_3") (pintype "output"))
      (node (ref "U19") (pin "3") (pinfunction "OUT_3") (pintype "output"))
      (node (ref "U20") (pin "3") (pinfunction "OUT_3") (pintype "output"))
      (node (ref "U21") (pin "3") (pinfunction "OUT_3") (pintype "output"))
      (node (ref "U22") (pin "3") (pinfunction "OUT_3") (pintype "output"))
      (node (ref "U23") (pin "3") (pinfunction "OUT_3") (pintype "output"))
      (node (ref "U24") (pin "3") (pinfunction "OUT_3") (pintype "output"))
      (node (ref "U25") (pin "3") (pinfunction "OUT_3") (pintype "output"))
    )
    (net (code "17") (name "ROW3") (class "Default")
      (node (ref "IC1") (pin "12") (pinfunction "X3_12") (pintype "bidirectional"))
      (node (ref "U26") (pin "3") (pinfunction "OUT_3") (pintype "output"))
      (node (ref "U27") (pin "3") (pinfunction "OUT_3") (pintype "output"))
      (node (ref "U28") (pin "3") (pinfunction "OUT_3") (pintype "output"))
      (node (ref "U29") (pin "3") (pinfunction "OUT_3") (pintype "output"))
      (node (ref "U30") (pin "3") (pinfunction "OUT_3") (pintype "output"))
      (node (ref "U31") (pin "3") (pinfunction "OUT_3") (pintype "output"))
      (node (ref "U32") (pin "3") (pinfunction "OUT_3") (pintype "output"))
      (node (ref "U33") (pin "3") (pinfunction "OUT_3") (pintype "output"))
    )
    (net (code "18") (name "ROW4") (class "Default")
      (node (ref "IC1") (pin "1") (pinfunction "X4_1") (pintype "bidirectional"))
      (node (ref "U34") (pin "3") (pinfunction "OUT_3") (pintype "output"))
      (node (ref "U35") (pin "3") (pinfunction "OUT_3") (pintype "output"))
      (node (ref "U36") (pin "3") (pinfunction "OUT_3") (pintype "output"))
      (node (ref "U37") (pin "3") (pinfunction "OUT_3") (pintype "output"))
      (node (ref "U38") (pin "3") (pinfunction "OUT_3") (pintype "output"))
      (node (ref "U39") (pin "3") (pinfunction "OUT_3") (pintype "output"))
      (node (ref "U40") (pin "3") (pinfunction "OUT_3") (pintype "output"))
      (node (ref "U41") (pin "3") (pinfunction "OUT_3") (pintype "output"))
    )
    (net (code "19") (name "ROW5") (class "Default")
      (node (ref "IC1") (pin "5") (pinfunction "X5_5") (pintype "bidirectional"))
      (node (ref "U42") (pin "3") (pinfunction "OUT_3") (pintype "output"))
      (node (ref "U43") (pin "3") (pinfunction "OUT_3") (pintype "output"))
      (node (ref "U44") (pin "3") (pinfunction "OUT_3") (pintype "output"))
      (node (ref "U45") (pin "3") (pinfunction "OUT_3") (pintype "output"))
      (node (ref "U46") (pin "3") (pinfunction "OUT_3") (pintype "output"))
      (node (ref "U47") (pin "3") (pinfunction "OUT_3") (pintype "output"))
      (node (ref "U48") (pin "3") (pinfunction "OUT_3") (pintype "output"))
      (node (ref "U49") (pin "3") (pinfunction "OUT_3") (pintype "output"))
    )
    (net (code "20") (name "ROW6") (class "Default")
      (node (ref "IC1") (pin "2") (pinfunction "X6_2") (pintype "bidirectional"))
      (node (ref "U50") (pin "3") (pinfunction "OUT_3") (pintype "output"))
      (node (ref "U51") (pin "3") (pinfunction "OUT_3") (pintype "output"))
      (node (ref "U52") (pin "3") (pinfunction "OUT_3") (pintype "output"))
      (node (ref "U53") (pin "3") (pinfunction "OUT_3") (pintype "output"))
      (node (ref "U54") (pin "3") (pinfunction "OUT_3") (pintype "output"))
      (node (ref "U55") (pin "3") (pinfunction "OUT_3") (pintype "output"))
      (node (ref "U56") (pin "3") (pinfunction "OUT_3") (pintype "output"))
      (node (ref "U57") (pin "3") (pinfunction "OUT_3") (pintype "output"))
    )
    (net (code "21") (name "ROW7") (class "Default")
      (node (ref "IC1") (pin "4") (pinfunction "X7_4") (pintype "bidirectional"))
      (node (ref "U58") (pin "3") (pinfunction "OUT_3") (pintype "output"))
      (node (ref "U59") (pin "3") (pinfunction "OUT_3") (pintype "output"))
      (node (ref "U60") (pin "3") (pinfunction "OUT_3") (pintype "output"))
      (node (ref "U61") (pin "3") (pinfunction "OUT_3") (pintype "output"))
      (node (ref "U62") (pin "3") (pinfunction "OUT_3") (pintype "output"))
      (node (ref "U63") (pin "3") (pinfunction "OUT_3") (pintype "output"))
      (node (ref "U64") (pin "3") (pinfunction "OUT_3") (pintype "output"))
      (node (ref "U65") (pin "3") (pinfunction "OUT_3") (pintype "output"))
    )
    (net (code "22") (name "unconnected-(IC1A-A-Pad11)") (class "Default")
      (node (ref "IC1") (pin "11") (pinfunction "A_11") (pintype "input"))
    )
    (net (code "23") (name "unconnected-(IC1A-B-Pad10)") (class "Default")
      (node (ref "IC1") (pin "10") (pinfunction "B_10") (pintype "input"))
    )
    (net (code "24") (name "unconnected-(IC1A-C-Pad9)") (class "Default")
      (node (ref "IC1") (pin "9") (pinfunction "C_9") (pintype "input"))
    )
    (net (code "25") (name "unconnected-(IC1A-INH-Pad6)") (class "Default")
      (node (ref "IC1") (pin "6") (pinfunction "INH_6") (pintype "input"))
    )
    (net (code "26") (name "unconnected-(IC1A-X-Pad3)") (class "Default")
      (node (ref "IC1") (pin "3") (pinfunction "X_3") (pintype "bidirectional"))
    )
    (net (code "27") (name "unconnected-(IC2A-A-Pad15)") (class "Default")
      (node (ref "IC2") (pin "15") (pinfunction "A_15") (pintype "input"))
    )
    (net (code "28") (name "unconnected-(IC2A-B-Pad14)") (class "Default")
      (node (ref "IC2") (pin "14") (pinfunction "B_14") (pintype "input"))
    )
    (net (code "29") (name "unconnected-(IC2A-C-Pad13)") (class "Default")
      (node (ref "IC2") (pin "13") (pinfunction "C_13") (pintype "input"))
    )
    (net (code "30") (name "unconnected-(IC2A-G1-Pad11)") (class "Default")
      (node (ref "IC2") (pin "11") (pinfunction "G1_11") (pintype "input"))
    )
    (net (code "31") (name "unconnected-(IC2A-G2A-Pad10)") (class "Default")
      (node (ref "IC2") (pin "10") (pinfunction "G2A_10") (pintype "input"))
    )
    (net (code "32") (name "unconnected-(IC2A-G2B-Pad9)") (class "Default")
      (node (ref "IC2") (pin "9") (pinfunction "G2B_9") (pintype "input"))
    )
    (net (code "33") (name "unconnected-(J1-Pad9)") (class "Default")
      (node (ref "J1") (pin "9") (pinfunction "9_9") (pintype "passive"))
    )
    (net (code "34") (name "unconnected-(J1-Pad10)") (class "Default")
      (node (ref "J1") (pin "10") (pinfunction "10_10") (pintype "passive"))
    )
    (net (code "35") (name "unconnected-(J1-Pad11)") (class "Default")
      (node (ref "J1") (pin "11") (pinfunction "11_11") (pintype "passive"))
    )
    (net (code "36") (name "unconnected-(J1-Pad12)") (class "Default")
      (node (ref "J1") (pin "12") (pinfunction "12_12") (pintype "passive"))
    )
    (net (code "37") (name "unconnected-(J1-Pad13)") (class "Default")
      (node (ref "J1") (pin "13") (pinfunction "13_13") (pintype "passive"))
    )
    (net (code "38") (name "unconnected-(J1-Pad14)") (class "Default")
      (node (ref "J1") (pin "14") (pinfunction "14_14") (pintype "passive"))
    )
    (net (code "39") (name "unconnected-(J1-Pad17)") (class "Default")
      (node (ref "J1") (pin "17") (pinfunction "17_17") (pintype "passive"))
    )
    (net (code "40") (name "unconnected-(J1-Pad18)") (class "Default")
      (node (ref "J1") (pin "18") (pinfunction "18_18") (pintype "passive"))
    )
    (net (code "41") (name "unconnected-(J1-Pad19)") (class "Default")
      (node (ref "J1") (pin "19") (pinfunction "19_19") (pintype "passive"))
    )
    (net (code "42") (name "unconnected-(J1-Pad20)") (class "Default")
      (node (ref "J1") (pin "20") (pinfunction "20_20") (pintype "passive"))
    )
    (net (code "43") (name "unconnected-(J1-Pad23)") (class "Default")
      (node (ref "J1") (pin "23") (pinfunction "23_23") (pintype "passive"))
    )
    (net (code "44") (name "unconnected-(J1-Pad24)") (class "Default")
      (node (ref "J1") (pin "24") (pinfunction "24_24") (pintype "passive"))
    )
    (net (code "45") (name "unconnected-(J1-Pad25)") (class "Default")
      (node (ref "J1") (pin "25") (pinfunction "25_25") (pintype "passive"))
    )
    (net (code "46") (name "unconnected-(J1-Pad26)") (class "Default")
      (node (ref "J1") (pin "26") (pinfunction "26_26") (pintype "passive"))
    )
    (net (code "47") (name "unconnected-(J1-Pad29)") (class "Default")
      (node (ref "J1") (pin "29") (pinfunction "29_29") (pintype "passive"))
    )
    (net (code "48") (name "unconnected-(J1-Pad30)") (class "Default")
      (node (ref "J1") (pin "30") (pinfunction "30_30") (pintype "passive"))
    )
    (net (code "49") (name "unconnected-(J1-Pad31)") (class "Default")
      (node (ref "J1") (pin "31") (pinfunction "31_31") (pintype "passive"))
    )
    (net (code "50") (name "unconnected-(J1-Pad32)") (class "Default")
      (node (ref "J1") (pin "32") (pinfunction "32_32") (pintype "passive"))
    )
    (net (code "51") (name "unconnected-(J1-Pad35)") (class "Default")
      (node (ref "J1") (pin "35") (pinfunction "35_35") (pintype "passive"))
    )
    (net (code "52") (name "unconnected-(J1-Pad36)") (class "Default")
      (node (ref "J1") (pin "36") (pinfunction "36_36") (pintype "passive"))
    )
    (net (code "53") (name "unconnected-(J1-Pad37)") (class "Default")
      (node (ref "J1") (pin "37") (pinfunction "37_37") (pintype "passive"))
    )
    (net (code "54") (name "unconnected-(J1-Pad38)") (class "Default")
      (node (ref "J1") (pin "38") (pinfunction "38_38") (pintype "passive"))
    )
    (net (code "55") (name "unconnected-(J1-Pad41)") (class "Default")
      (node (ref "J1") (pin "41") (pinfunction "41_41") (pintype "passive"))
    )
    (net (code "56") (name "unconnected-(J1-Pad42)") (class "Default")
      (node (ref "J1") (pin "42") (pinfunction "42_42") (pintype "passive"))
    )
    (net (code "57") (name "unconnected-(J1-Pad43)") (class "Default")
      (node (ref "J1") (pin "43") (pinfunction "43_43") (pintype "passive"))
    )
    (net (code "58") (name "unconnected-(J1-Pad44)") (class "Default")
      (node (ref "J1") (pin "44") (pinfunction "44_44") (pintype "passive"))
    )
    (net (code "59") (name "unconnected-(J1-Pad47)") (class "Default")
      (node (ref "J1") (pin "47") (pinfunction "47_47") (pintype "passive"))
    )
    (net (code "60") (name "unconnected-(J1-Pad48)") (class "Default")
      (node (ref "J1") (pin "48") (pinfunction "48_48") (pintype "passive"))
    )
    (net (code "61") (name "unconnected-(J1-Pad49)") (class "Default")
      (node (ref "J1") (pin "49") (pinfunction "49_49") (pintype "passive"))
    )
    (net (code "62") (name "unconnected-(J1-Pad50)") (class "Default")
      (node (ref "J1") (pin "50") (pinfunction "50_50") (pintype "passive"))
    )
    (net (code "63") (name "unconnected-(J1-Pad53)") (class "Default")
      (node (ref "J1") (pin "53") (pinfunction "53_53") (pintype "passive"))
    )
    (net (code "64") (name "unconnected-(J1-Pad54)") (class "Default")
      (node (ref "J1") (pin "54") (pinfunction "54_54") (pintype "passive"))
    )
    (net (code "65") (name "unconnected-(J1-Pad55)") (class "Default")
      (node (ref "J1") (pin "55") (pinfunction "55_55") (pintype "passive"))
    )
    (net (code "66") (name "unconnected-(J1-Pad56)") (class "Default")
      (node (ref "J1") (pin "56") (pinfunction "56_56") (pintype "passive"))
    )
    (net (code "67") (name "unconnected-(J1-Pad59)") (class "Default")
      (node (ref "J1") (pin "59") (pinfunction "59_59") (pintype "passive"))
    )
    (net (code "68") (name "unconnected-(J1-Pad60)") (class "Default")
      (node (ref "J1") (pin "60") (pinfunction "60_60") (pintype "passive"))
    )
    (net (code "69") (name "unconnected-(J1-Pad61)") (class "Default")
      (node (ref "J1") (pin "61") (pinfunction "61_61") (pintype "passive"))
    )
    (net (code "70") (name "unconnected-(J1-Pad62)") (class "Default")
      (node (ref "J1") (pin "62") (pinfunction "62_62") (pintype "passive"))
    )
    (net (code "71") (name "unconnected-(J1-Pad65)") (class "Default")
      (node (ref "J1") (pin "65") (pinfunction "65_65") (pintype "passive"))
    )
    (net (code "72") (name "unconnected-(J1-Pad66)") (class "Default")
      (node (ref "J1") (pin "66") (pinfunction "66_66") (pintype "passive"))
    )
    (net (code "73") (name "unconnected-(J1-Pad67)") (class "Default")
      (node (ref "J1") (pin "67") (pinfunction "67_67") (pintype "passive"))
    )
    (net (code "74") (name "unconnected-(J1-Pad68)") (class "Default")
      (node (ref "J1") (pin "68") (pinfunction "68_68") (pintype "passive"))
    )
    (net (code "75") (name "unconnected-(U5-PG-Pad6)") (class "Default")
      (node (ref "U5") (pin "6") (pinfunction "PG_6") (pintype "bidirectional"))
    )
  )
)
